# MCU025B_F280049C_Device.net
KiCad netlist of a schematic drawn in Altium Designer
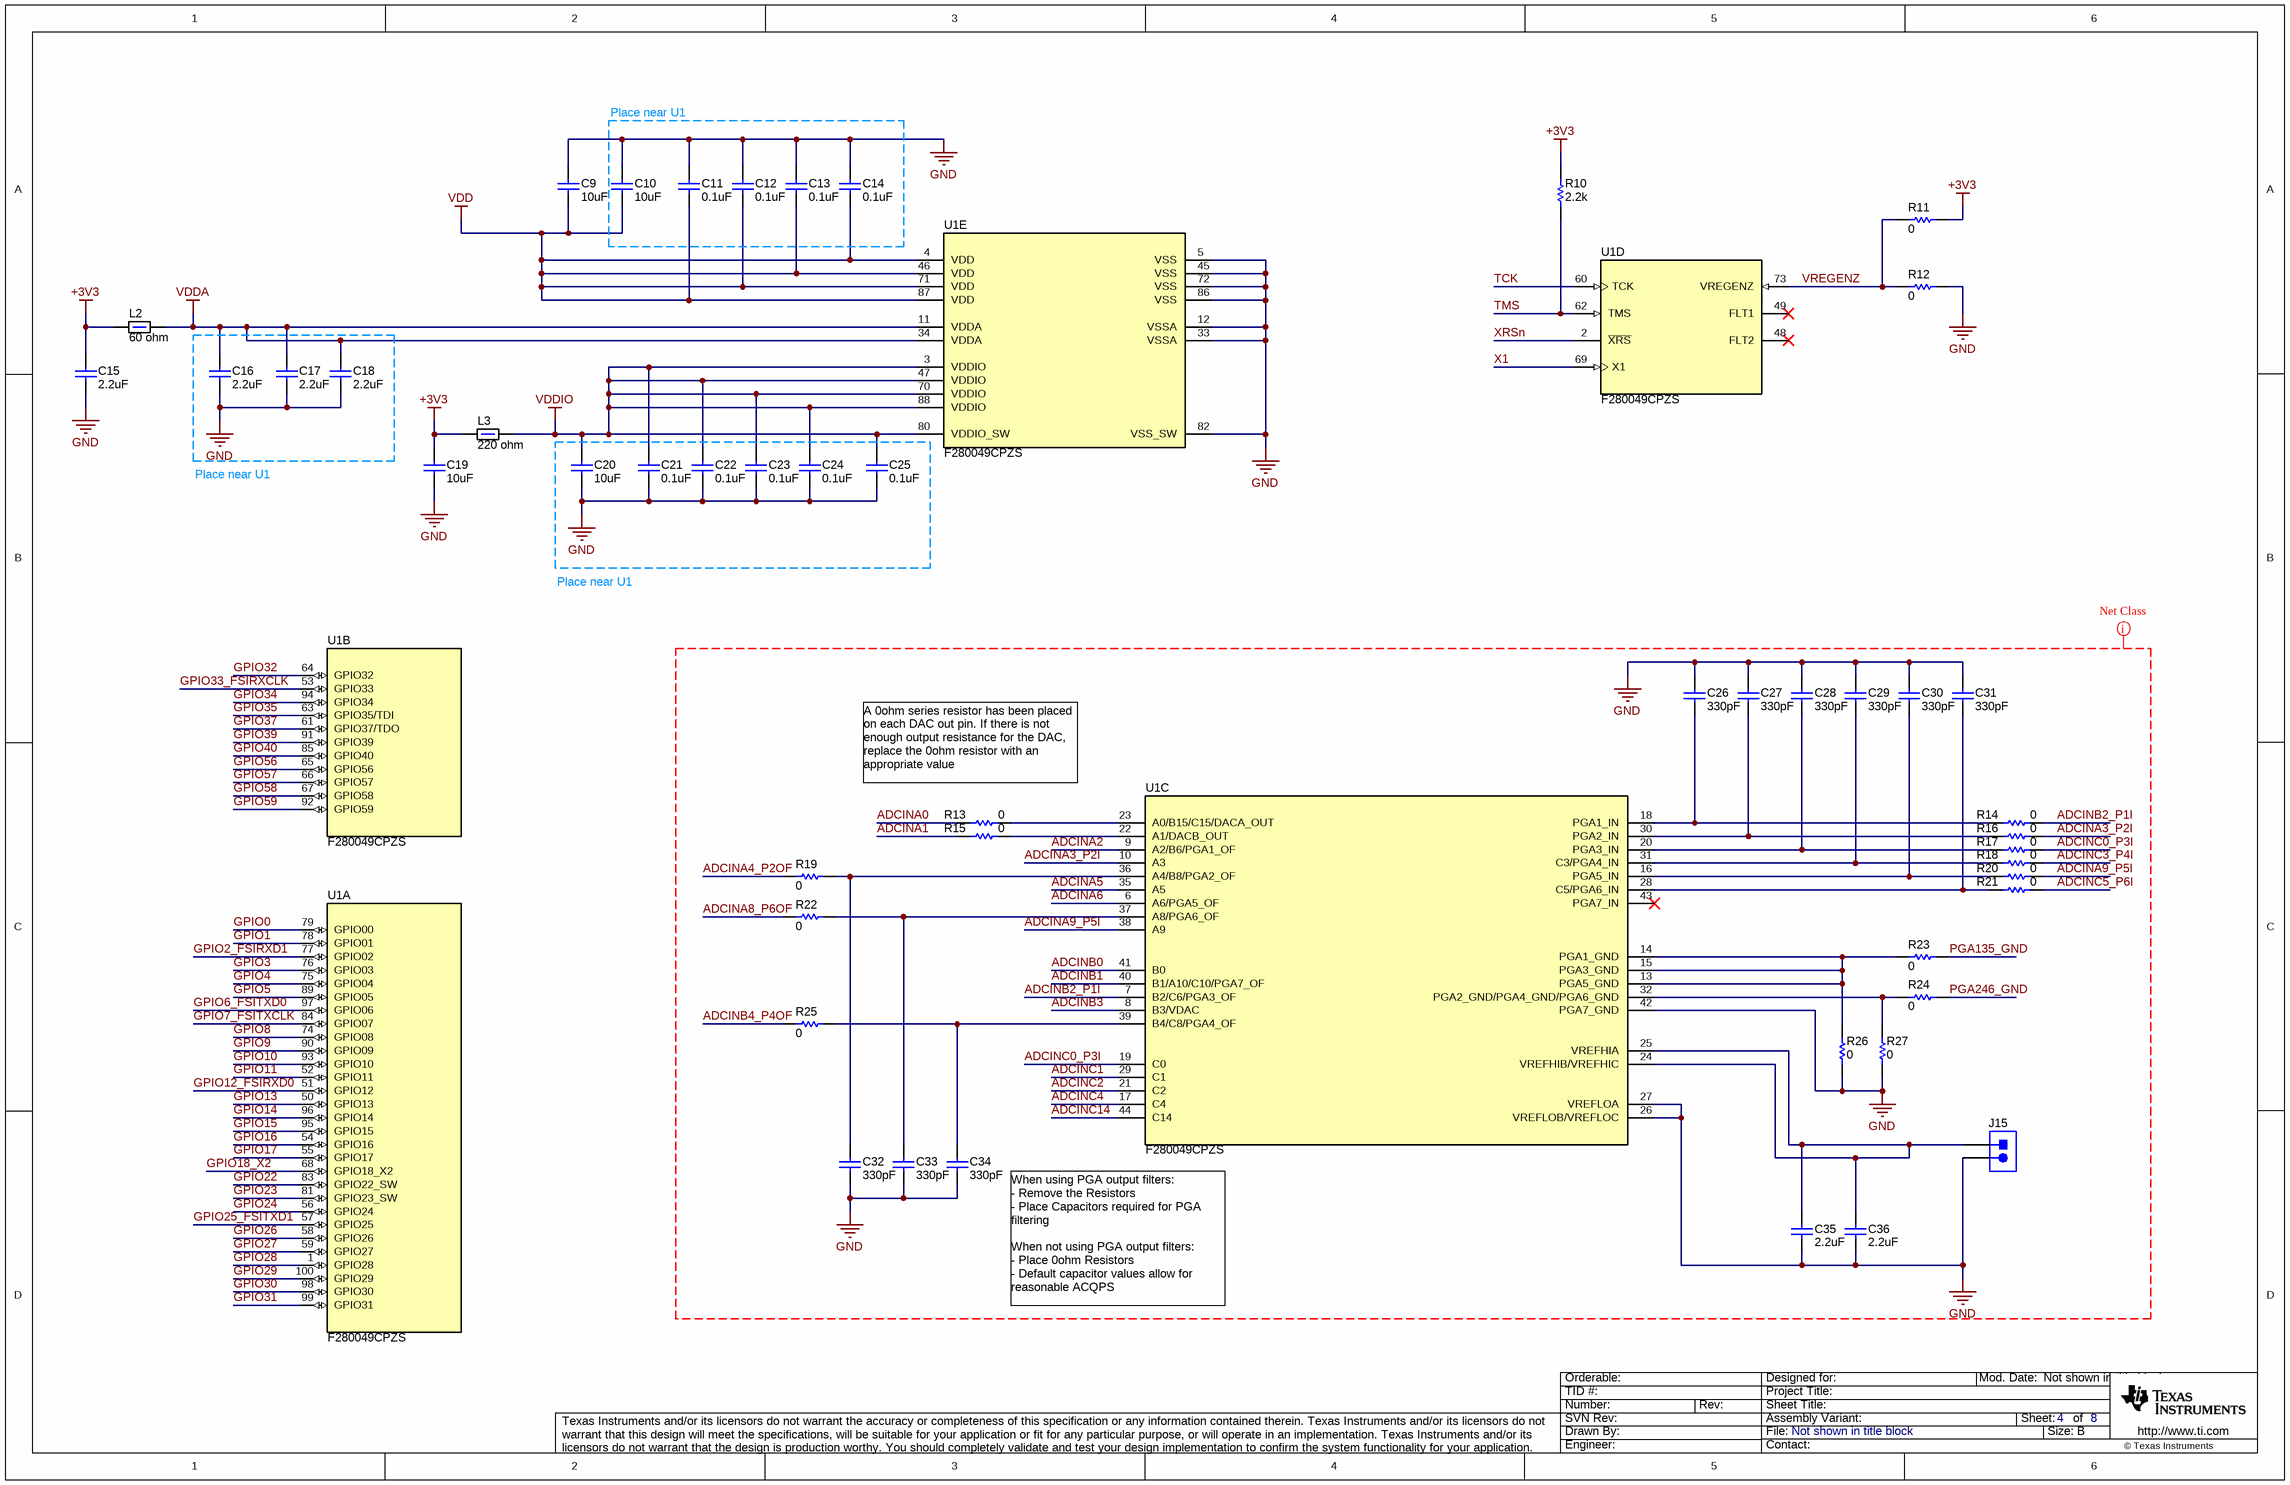
[diagram p0: MCU025B_F280049C_Device.SchDoc]

(export (version "E")
  (design (tool "Eeschema 10.0.6"))
  (components
    (comp (ref "C9")
      (value "GRM188R61A106ME69D")
      (footprint "0603")
      (description "CAP, CERM, 10 uF, 10 V, +/- 20%, X5R, 0603")
      (fields
        (field (name "VALUEDISPLAYED") "10uF")
        (field (name "MANUFACTURER") "MuRata")
        (field (name "PUBLISHER") "Texas Instruments")
      )
      (libsource (lib "Altium Vault - TI") (part "Capacitor"))
    )
    (comp (ref "C10")
      (value "GRM188R61A106ME69D")
      (footprint "0603")
      (description "CAP, CERM, 10 uF, 10 V, +/- 20%, X5R, 0603")
      (fields
        (field (name "VALUEDISPLAYED") "10uF")
        (field (name "MANUFACTURER") "MuRata")
        (field (name "PUBLISHER") "Texas Instruments")
      )
      (libsource (lib "Altium Vault - TI") (part "Capacitor"))
    )
    (comp (ref "C11")
      (value "GRM155R71A104KA01D")
      (footprint "0402")
      (description "CAP, CERM, 0.1 uF, 10 V, +/- 10%, X7R, 0402")
      (fields
        (field (name "VALUEDISPLAYED") "0.1uF")
        (field (name "MANUFACTURER") "MuRata")
        (field (name "PUBLISHER") "Texas Instruments")
      )
      (libsource (lib "Altium Vault - TI") (part "Capacitor"))
    )
    (comp (ref "C12")
      (value "GRM155R71A104KA01D")
      (footprint "0402")
      (description "CAP, CERM, 0.1 uF, 10 V, +/- 10%, X7R, 0402")
      (fields
        (field (name "VALUEDISPLAYED") "0.1uF")
        (field (name "MANUFACTURER") "MuRata")
        (field (name "PUBLISHER") "Texas Instruments")
      )
      (libsource (lib "Altium Vault - TI") (part "Capacitor"))
    )
    (comp (ref "C13")
      (value "GRM155R71A104KA01D")
      (footprint "0402")
      (description "CAP, CERM, 0.1 uF, 10 V, +/- 10%, X7R, 0402")
      (fields
        (field (name "VALUEDISPLAYED") "0.1uF")
        (field (name "MANUFACTURER") "MuRata")
        (field (name "PUBLISHER") "Texas Instruments")
      )
      (libsource (lib "Altium Vault - TI") (part "Capacitor"))
    )
    (comp (ref "C14")
      (value "GRM155R71A104KA01D")
      (footprint "0402")
      (description "CAP, CERM, 0.1 uF, 10 V, +/- 10%, X7R, 0402")
      (fields
        (field (name "VALUEDISPLAYED") "0.1uF")
        (field (name "MANUFACTURER") "MuRata")
        (field (name "PUBLISHER") "Texas Instruments")
      )
      (libsource (lib "Altium Vault - TI") (part "Capacitor"))
    )
    (comp (ref "C15")
      (value "GRM188R61A225KE34D")
      (footprint "0603")
      (description "CAP, CERM, 2.2 uF, 10 V, +/- 10%, X5R, 0603")
      (fields
        (field (name "VALUEDISPLAYED") "2.2uF")
        (field (name "MANUFACTURER") "MuRata")
        (field (name "PUBLISHER") "Texas Instruments")
      )
      (libsource (lib "Altium Vault - TI") (part "Capacitor"))
    )
    (comp (ref "C16")
      (value "GRM188R61A225KE34D")
      (footprint "0603")
      (description "CAP, CERM, 2.2 uF, 10 V, +/- 10%, X5R, 0603")
      (fields
        (field (name "VALUEDISPLAYED") "2.2uF")
        (field (name "MANUFACTURER") "MuRata")
        (field (name "PUBLISHER") "Texas Instruments")
      )
      (libsource (lib "Altium Vault - TI") (part "Capacitor"))
    )
    (comp (ref "C17")
      (value "GRM188R61A225KE34D")
      (footprint "0603")
      (description "CAP, CERM, 2.2 uF, 10 V, +/- 10%, X5R, 0603")
      (fields
        (field (name "VALUEDISPLAYED") "2.2uF")
        (field (name "MANUFACTURER") "MuRata")
        (field (name "PUBLISHER") "Texas Instruments")
      )
      (libsource (lib "Altium Vault - TI") (part "Capacitor"))
    )
    (comp (ref "C18")
      (value "GRM188R61A225KE34D")
      (footprint "0603")
      (description "CAP, CERM, 2.2 uF, 10 V, +/- 10%, X5R, 0603")
      (fields
        (field (name "VALUEDISPLAYED") "2.2uF")
        (field (name "MANUFACTURER") "MuRata")
        (field (name "PUBLISHER") "Texas Instruments")
      )
      (libsource (lib "Altium Vault - TI") (part "Capacitor"))
    )
    (comp (ref "C19")
      (value "GRM188R61A106ME69D")
      (footprint "0603")
      (description "CAP, CERM, 10 uF, 10 V, +/- 20%, X5R, 0603")
      (fields
        (field (name "VALUEDISPLAYED") "10uF")
        (field (name "MANUFACTURER") "MuRata")
        (field (name "PUBLISHER") "Texas Instruments")
      )
      (libsource (lib "Altium Vault - TI") (part "Capacitor"))
    )
    (comp (ref "C20")
      (value "GRM188R61A106ME69D")
      (footprint "0603")
      (description "CAP, CERM, 10 uF, 10 V, +/- 20%, X5R, 0603")
      (fields
        (field (name "VALUEDISPLAYED") "10uF")
        (field (name "MANUFACTURER") "MuRata")
        (field (name "PUBLISHER") "Texas Instruments")
      )
      (libsource (lib "Altium Vault - TI") (part "Capacitor"))
    )
    (comp (ref "C21")
      (value "GRM155R71A104KA01D")
      (footprint "0402")
      (description "CAP, CERM, 0.1 uF, 10 V, +/- 10%, X7R, 0402")
      (fields
        (field (name "VALUEDISPLAYED") "0.1uF")
        (field (name "MANUFACTURER") "MuRata")
        (field (name "PUBLISHER") "Texas Instruments")
      )
      (libsource (lib "Altium Vault - TI") (part "Capacitor"))
    )
    (comp (ref "C22")
      (value "GRM155R71A104KA01D")
      (footprint "0402")
      (description "CAP, CERM, 0.1 uF, 10 V, +/- 10%, X7R, 0402")
      (fields
        (field (name "VALUEDISPLAYED") "0.1uF")
        (field (name "MANUFACTURER") "MuRata")
        (field (name "PUBLISHER") "Texas Instruments")
      )
      (libsource (lib "Altium Vault - TI") (part "Capacitor"))
    )
    (comp (ref "C23")
      (value "GRM155R71A104KA01D")
      (footprint "0402")
      (description "CAP, CERM, 0.1 uF, 10 V, +/- 10%, X7R, 0402")
      (fields
        (field (name "VALUEDISPLAYED") "0.1uF")
        (field (name "MANUFACTURER") "MuRata")
        (field (name "PUBLISHER") "Texas Instruments")
      )
      (libsource (lib "Altium Vault - TI") (part "Capacitor"))
    )
    (comp (ref "C24")
      (value "GRM155R71A104KA01D")
      (footprint "0402")
      (description "CAP, CERM, 0.1 uF, 10 V, +/- 10%, X7R, 0402")
      (fields
        (field (name "VALUEDISPLAYED") "0.1uF")
        (field (name "MANUFACTURER") "MuRata")
        (field (name "PUBLISHER") "Texas Instruments")
      )
      (libsource (lib "Altium Vault - TI") (part "Capacitor"))
    )
    (comp (ref "C25")
      (value "GRM155R71A104KA01D")
      (footprint "0402")
      (description "CAP, CERM, 0.1 uF, 10 V, +/- 10%, X7R, 0402")
      (fields
        (field (name "VALUEDISPLAYED") "0.1uF")
        (field (name "MANUFACTURER") "MuRata")
        (field (name "PUBLISHER") "Texas Instruments")
      )
      (libsource (lib "Altium Vault - TI") (part "Capacitor"))
    )
    (comp (ref "C26")
      (value "GRM1885C1H331JA01D")
      (footprint "0603")
      (description "CAP, CERM, 330 pF, 50 V, +/- 5%, C0G/NP0, 0603")
      (fields
        (field (name "VALUEDISPLAYED") "330pF")
        (field (name "MANUFACTURER") "MuRata")
        (field (name "PUBLISHER") "Texas Instruments")
      )
      (libsource (lib "Altium Vault - TI") (part "Capacitor"))
    )
    (comp (ref "C27")
      (value "GRM1885C1H331JA01D")
      (footprint "0603")
      (description "CAP, CERM, 330 pF, 50 V, +/- 5%, C0G/NP0, 0603")
      (fields
        (field (name "VALUEDISPLAYED") "330pF")
        (field (name "MANUFACTURER") "MuRata")
        (field (name "PUBLISHER") "Texas Instruments")
      )
      (libsource (lib "Altium Vault - TI") (part "Capacitor"))
    )
    (comp (ref "C28")
      (value "GRM1885C1H331JA01D")
      (footprint "0603")
      (description "CAP, CERM, 330 pF, 50 V, +/- 5%, C0G/NP0, 0603")
      (fields
        (field (name "VALUEDISPLAYED") "330pF")
        (field (name "MANUFACTURER") "MuRata")
        (field (name "PUBLISHER") "Texas Instruments")
      )
      (libsource (lib "Altium Vault - TI") (part "Capacitor"))
    )
    (comp (ref "C29")
      (value "GRM1885C1H331JA01D")
      (footprint "0603")
      (description "CAP, CERM, 330 pF, 50 V, +/- 5%, C0G/NP0, 0603")
      (fields
        (field (name "VALUEDISPLAYED") "330pF")
        (field (name "MANUFACTURER") "MuRata")
        (field (name "PUBLISHER") "Texas Instruments")
      )
      (libsource (lib "Altium Vault - TI") (part "Capacitor"))
    )
    (comp (ref "C30")
      (value "GRM1885C1H331JA01D")
      (footprint "0603")
      (description "CAP, CERM, 330 pF, 50 V, +/- 5%, C0G/NP0, 0603")
      (fields
        (field (name "VALUEDISPLAYED") "330pF")
        (field (name "MANUFACTURER") "MuRata")
        (field (name "PUBLISHER") "Texas Instruments")
      )
      (libsource (lib "Altium Vault - TI") (part "Capacitor"))
    )
    (comp (ref "C31")
      (value "GRM1885C1H331JA01D")
      (footprint "0603")
      (description "CAP, CERM, 330 pF, 50 V, +/- 5%, C0G/NP0, 0603")
      (fields
        (field (name "VALUEDISPLAYED") "330pF")
        (field (name "MANUFACTURER") "MuRata")
        (field (name "PUBLISHER") "Texas Instruments")
      )
      (libsource (lib "Altium Vault - TI") (part "Capacitor"))
    )
    (comp (ref "C32")
      (value "GRM1885C1H331JA01D")
      (footprint "0603")
      (description "CAP, CERM, 330 pF, 50 V, +/- 5%, C0G/NP0, 0603")
      (fields
        (field (name "VALUEDISPLAYED") "330pF")
        (field (name "MANUFACTURER") "MuRata")
        (field (name "PUBLISHER") "Texas Instruments")
      )
      (libsource (lib "Altium Vault - TI") (part "Capacitor"))
    )
    (comp (ref "C33")
      (value "GRM1885C1H331JA01D")
      (footprint "0603")
      (description "CAP, CERM, 330 pF, 50 V, +/- 5%, C0G/NP0, 0603")
      (fields
        (field (name "VALUEDISPLAYED") "330pF")
        (field (name "MANUFACTURER") "MuRata")
        (field (name "PUBLISHER") "Texas Instruments")
      )
      (libsource (lib "Altium Vault - TI") (part "Capacitor"))
    )
    (comp (ref "C34")
      (value "GRM1885C1H331JA01D")
      (footprint "0603")
      (description "CAP, CERM, 330 pF, 50 V, +/- 5%, C0G/NP0, 0603")
      (fields
        (field (name "VALUEDISPLAYED") "330pF")
        (field (name "MANUFACTURER") "MuRata")
        (field (name "PUBLISHER") "Texas Instruments")
      )
      (libsource (lib "Altium Vault - TI") (part "Capacitor"))
    )
    (comp (ref "C35")
      (value "GRM188R61A225KE34D")
      (footprint "0603")
      (description "CAP, CERM, 2.2 uF, 10 V, +/- 10%, X5R, 0603")
      (fields
        (field (name "VALUEDISPLAYED") "2.2uF")
        (field (name "MANUFACTURER") "MuRata")
        (field (name "PUBLISHER") "Texas Instruments")
      )
      (libsource (lib "Altium Vault - TI") (part "Capacitor"))
    )
    (comp (ref "C36")
      (value "GRM188R61A225KE34D")
      (footprint "0603")
      (description "CAP, CERM, 2.2 uF, 10 V, +/- 10%, X5R, 0603")
      (fields
        (field (name "VALUEDISPLAYED") "2.2uF")
        (field (name "MANUFACTURER") "MuRata")
        (field (name "PUBLISHER") "Texas Instruments")
      )
      (libsource (lib "Altium Vault - TI") (part "Capacitor"))
    )
    (comp (ref "J15")
      (value "61300211121")
      (footprint "WURTH_61300211121")
      (description "Header, 2.54 mm, 2x1, Gold, TH")
      (fields (field (name "MANUFACTURER") "Wurth Elektronik") (field (name "PUBLISHER") "Texas Instruments"))
      (libsource (lib "Altium Vault - TI") (part "CMP-0054794-1"))
    )
    (comp (ref "L2")
      (value "BKP2125HS600-T")
      (footprint "0805")
      (description "Ferrite Bead, 60 ohm @ 100 MHz, 3 A, 0805")
      (fields
        (field (name "VALUEDISPLAYED") "60 ohm")
        (field (name "MANUFACTURER") "Taiyo Yuden")
        (field (name "PUBLISHER") "Texas Instruments")
      )
      (libsource (lib "Altium Vault - TI") (part "Ferrite_Bead"))
    )
    (comp (ref "L3")
      (value "BLM21PG221SN1D")
      (footprint "0805")
      (description "Ferrite Bead, 220 ohm @ 100 MHz, 2 A, 0805")
      (fields
        (field (name "VALUEDISPLAYED") "220 ohm")
        (field (name "MANUFACTURER") "MuRata")
        (field (name "PUBLISHER") "Texas Instruments")
      )
      (libsource (lib "Altium Vault - TI") (part "Ferrite_Bead"))
    )
    (comp (ref "R10")
      (value "CRCW04022K20JNED")
      (footprint "0402")
      (description "RES, 2.2 k, 5%, 0.063 W, AEC-Q200 Grade 0, 0402")
      (fields (field (name "VALUEDISPLAYED") "2.2k") (field (name "MANUFACTURER") "Vishay-Dale"))
      (libsource (lib "Altium Vault - TI") (part "Resistor"))
    )
    (comp (ref "R11")
      (value "CRCW06030000Z0EA")
      (footprint "0603")
      (description "RES, 0, 5%, 0.1 W, AEC-Q200 Grade 0, 0603")
      (fields (field (name "VALUEDISPLAYED") "0") (field (name "MANUFACTURER") "Vishay-Dale"))
      (libsource (lib "Altium Vault - TI") (part "Resistor"))
    )
    (comp (ref "R12")
      (value "CRCW06030000Z0EA")
      (footprint "0603")
      (description "RES, 0, 5%, 0.1 W, AEC-Q200 Grade 0, 0603")
      (fields (field (name "VALUEDISPLAYED") "0") (field (name "MANUFACTURER") "Vishay-Dale"))
      (libsource (lib "Altium Vault - TI") (part "Resistor"))
    )
    (comp (ref "R13")
      (value "CRCW06030000Z0EA")
      (footprint "0603")
      (description "RES, 0, 5%, 0.1 W, AEC-Q200 Grade 0, 0603")
      (fields (field (name "VALUEDISPLAYED") "0") (field (name "MANUFACTURER") "Vishay-Dale"))
      (libsource (lib "Altium Vault - TI") (part "Resistor"))
    )
    (comp (ref "R14")
      (value "CRCW06030000Z0EA")
      (footprint "0603")
      (description "RES, 0, 5%, 0.1 W, AEC-Q200 Grade 0, 0603")
      (fields (field (name "VALUEDISPLAYED") "0") (field (name "MANUFACTURER") "Vishay-Dale"))
      (libsource (lib "Altium Vault - TI") (part "Resistor"))
    )
    (comp (ref "R15")
      (value "CRCW06030000Z0EA")
      (footprint "0603")
      (description "RES, 0, 5%, 0.1 W, AEC-Q200 Grade 0, 0603")
      (fields (field (name "VALUEDISPLAYED") "0") (field (name "MANUFACTURER") "Vishay-Dale"))
      (libsource (lib "Altium Vault - TI") (part "Resistor"))
    )
    (comp (ref "R16")
      (value "CRCW06030000Z0EA")
      (footprint "0603")
      (description "RES, 0, 5%, 0.1 W, AEC-Q200 Grade 0, 0603")
      (fields (field (name "VALUEDISPLAYED") "0") (field (name "MANUFACTURER") "Vishay-Dale"))
      (libsource (lib "Altium Vault - TI") (part "Resistor"))
    )
    (comp (ref "R17")
      (value "CRCW06030000Z0EA")
      (footprint "0603")
      (description "RES, 0, 5%, 0.1 W, AEC-Q200 Grade 0, 0603")
      (fields (field (name "VALUEDISPLAYED") "0") (field (name "MANUFACTURER") "Vishay-Dale"))
      (libsource (lib "Altium Vault - TI") (part "Resistor"))
    )
    (comp (ref "R18")
      (value "CRCW06030000Z0EA")
      (footprint "0603")
      (description "RES, 0, 5%, 0.1 W, AEC-Q200 Grade 0, 0603")
      (fields (field (name "VALUEDISPLAYED") "0") (field (name "MANUFACTURER") "Vishay-Dale"))
      (libsource (lib "Altium Vault - TI") (part "Resistor"))
    )
    (comp (ref "R19")
      (value "CRCW06030000Z0EA")
      (footprint "0603")
      (description "RES, 0, 5%, 0.1 W, AEC-Q200 Grade 0, 0603")
      (fields (field (name "VALUEDISPLAYED") "0") (field (name "MANUFACTURER") "Vishay-Dale"))
      (libsource (lib "Altium Vault - TI") (part "Resistor"))
    )
    (comp (ref "R20")
      (value "CRCW06030000Z0EA")
      (footprint "0603")
      (description "RES, 0, 5%, 0.1 W, AEC-Q200 Grade 0, 0603")
      (fields (field (name "VALUEDISPLAYED") "0") (field (name "MANUFACTURER") "Vishay-Dale"))
      (libsource (lib "Altium Vault - TI") (part "Resistor"))
    )
    (comp (ref "R21")
      (value "CRCW06030000Z0EA")
      (footprint "0603")
      (description "RES, 0, 5%, 0.1 W, AEC-Q200 Grade 0, 0603")
      (fields (field (name "VALUEDISPLAYED") "0") (field (name "MANUFACTURER") "Vishay-Dale"))
      (libsource (lib "Altium Vault - TI") (part "Resistor"))
    )
    (comp (ref "R22")
      (value "CRCW06030000Z0EA")
      (footprint "0603")
      (description "RES, 0, 5%, 0.1 W, AEC-Q200 Grade 0, 0603")
      (fields (field (name "VALUEDISPLAYED") "0") (field (name "MANUFACTURER") "Vishay-Dale"))
      (libsource (lib "Altium Vault - TI") (part "Resistor"))
    )
    (comp (ref "R23")
      (value "CRCW06030000Z0EA")
      (footprint "0603")
      (description "RES, 0, 5%, 0.1 W, AEC-Q200 Grade 0, 0603")
      (fields (field (name "VALUEDISPLAYED") "0") (field (name "MANUFACTURER") "Vishay-Dale"))
      (libsource (lib "Altium Vault - TI") (part "Resistor"))
    )
    (comp (ref "R24")
      (value "CRCW06030000Z0EA")
      (footprint "0603")
      (description "RES, 0, 5%, 0.1 W, AEC-Q200 Grade 0, 0603")
      (fields (field (name "VALUEDISPLAYED") "0") (field (name "MANUFACTURER") "Vishay-Dale"))
      (libsource (lib "Altium Vault - TI") (part "Resistor"))
    )
    (comp (ref "R25")
      (value "CRCW06030000Z0EA")
      (footprint "0603")
      (description "RES, 0, 5%, 0.1 W, AEC-Q200 Grade 0, 0603")
      (fields (field (name "VALUEDISPLAYED") "0") (field (name "MANUFACTURER") "Vishay-Dale"))
      (libsource (lib "Altium Vault - TI") (part "Resistor"))
    )
    (comp (ref "R26")
      (value "CRCW06030000Z0EA")
      (footprint "0603")
      (description "RES, 0, 5%, 0.1 W, AEC-Q200 Grade 0, 0603")
      (fields (field (name "VALUEDISPLAYED") "0") (field (name "MANUFACTURER") "Vishay-Dale"))
      (libsource (lib "Altium Vault - TI") (part "Resistor"))
    )
    (comp (ref "R27")
      (value "CRCW06030000Z0EA")
      (footprint "0603")
      (description "RES, 0, 5%, 0.1 W, AEC-Q200 Grade 0, 0603")
      (fields (field (name "VALUEDISPLAYED") "0") (field (name "MANUFACTURER") "Vishay-Dale"))
      (libsource (lib "Altium Vault - TI") (part "Resistor"))
    )
    (comp (ref "U1")
      (value "F280049CPZS")
      (footprint "PZ0100A_N")
      (description "Piccolo Microcontroller, PZ0100A (LQFP-100)")
      (fields (field (name "PARTNUMBER") "F280049CPZS") (field (name "MANUFACTURER") "Texas Instruments"))
      (libsource (lib "Altium Vault - TI") (part "F280049PZ"))
    )
  )
  (nets
    (net (code "1") (name "+3V3") (class "Default")
      (node (ref "C15") (pin "1") (pinfunction "1_1") (pintype "passive"))
      (node (ref "C19") (pin "1") (pinfunction "1_1") (pintype "passive"))
      (node (ref "L2") (pin "1") (pinfunction "1_1") (pintype "passive"))
      (node (ref "L3") (pin "1") (pinfunction "1_1") (pintype "passive"))
      (node (ref "R10") (pin "2") (pinfunction "2_2") (pintype "passive"))
      (node (ref "R11") (pin "2") (pinfunction "2_2") (pintype "passive"))
    )
    (net (code "2") (name "/ADCINA0") (class "Default")
      (node (ref "R13") (pin "1") (pinfunction "1_1") (pintype "passive"))
    )
    (net (code "3") (name "/ADCINA1") (class "Default")
      (node (ref "R15") (pin "1") (pinfunction "1_1") (pintype "passive"))
    )
    (net (code "4") (name "/ADCINA2") (class "Default")
      (node (ref "U1") (pin "9") (pinfunction "A2/B6/PGA1_OF_9") (pintype "passive"))
    )
    (net (code "5") (name "/ADCINA3_P2I") (class "Default")
      (node (ref "R16") (pin "2") (pinfunction "2_2") (pintype "passive"))
      (node (ref "U1") (pin "10") (pinfunction "A3_10") (pintype "passive"))
    )
    (net (code "6") (name "/ADCINA4_P2OF") (class "Default")
      (node (ref "R19") (pin "1") (pinfunction "1_1") (pintype "passive"))
    )
    (net (code "7") (name "/ADCINA5") (class "Default")
      (node (ref "U1") (pin "35") (pinfunction "A5_35") (pintype "passive"))
    )
    (net (code "8") (name "/ADCINA6") (class "Default")
      (node (ref "U1") (pin "6") (pinfunction "A6/PGA5_OF_6") (pintype "passive"))
    )
    (net (code "9") (name "/ADCINA8_P6OF") (class "Default")
      (node (ref "R22") (pin "1") (pinfunction "1_1") (pintype "passive"))
    )
    (net (code "10") (name "/ADCINA9_P5I") (class "Default")
      (node (ref "R20") (pin "2") (pinfunction "2_2") (pintype "passive"))
      (node (ref "U1") (pin "38") (pinfunction "A9_38") (pintype "passive"))
    )
    (net (code "11") (name "/ADCINB0") (class "Default")
      (node (ref "U1") (pin "41") (pinfunction "B0_41") (pintype "passive"))
    )
    (net (code "12") (name "/ADCINB1") (class "Default")
      (node (ref "U1") (pin "40") (pinfunction "B1/A10/C10/PGA7_OF_40") (pintype "passive"))
    )
    (net (code "13") (name "/ADCINB2_P1I") (class "Default")
      (node (ref "R14") (pin "2") (pinfunction "2_2") (pintype "passive"))
      (node (ref "U1") (pin "7") (pinfunction "B2/C6/PGA3_OF_7") (pintype "passive"))
    )
    (net (code "14") (name "/ADCINB3") (class "Default")
      (node (ref "U1") (pin "8") (pinfunction "B3/VDAC_8") (pintype "passive"))
    )
    (net (code "15") (name "/ADCINB4_P4OF") (class "Default")
      (node (ref "R25") (pin "1") (pinfunction "1_1") (pintype "passive"))
    )
    (net (code "16") (name "/ADCINC0_P3I") (class "Default")
      (node (ref "R17") (pin "2") (pinfunction "2_2") (pintype "passive"))
      (node (ref "U1") (pin "19") (pinfunction "C0_19") (pintype "passive"))
    )
    (net (code "17") (name "/ADCINC1") (class "Default")
      (node (ref "U1") (pin "29") (pinfunction "C1_29") (pintype "passive"))
    )
    (net (code "18") (name "/ADCINC2") (class "Default")
      (node (ref "U1") (pin "21") (pinfunction "C2_21") (pintype "passive"))
    )
    (net (code "19") (name "/ADCINC3_P4I") (class "Default")
      (node (ref "R18") (pin "2") (pinfunction "2_2") (pintype "passive"))
    )
    (net (code "20") (name "/ADCINC4") (class "Default")
      (node (ref "U1") (pin "17") (pinfunction "C4_17") (pintype "passive"))
    )
    (net (code "21") (name "/ADCINC5_P6I") (class "Default")
      (node (ref "R21") (pin "2") (pinfunction "2_2") (pintype "passive"))
    )
    (net (code "22") (name "/ADCINC14") (class "Default")
      (node (ref "U1") (pin "44") (pinfunction "C14_44") (pintype "passive"))
    )
    (net (code "23") (name "/GPIO0") (class "Default")
      (node (ref "U1") (pin "79") (pinfunction "GPIO00_79") (pintype "bidirectional"))
    )
    (net (code "24") (name "/GPIO1") (class "Default")
      (node (ref "U1") (pin "78") (pinfunction "GPIO01_78") (pintype "bidirectional"))
    )
    (net (code "25") (name "/GPIO2_FSIRXD1") (class "Default")
      (node (ref "U1") (pin "77") (pinfunction "GPIO02_77") (pintype "bidirectional"))
    )
    (net (code "26") (name "/GPIO3") (class "Default")
      (node (ref "U1") (pin "76") (pinfunction "GPIO03_76") (pintype "bidirectional"))
    )
    (net (code "27") (name "/GPIO4") (class "Default")
      (node (ref "U1") (pin "75") (pinfunction "GPIO04_75") (pintype "bidirectional"))
    )
    (net (code "28") (name "/GPIO5") (class "Default")
      (node (ref "U1") (pin "89") (pinfunction "GPIO05_89") (pintype "bidirectional"))
    )
    (net (code "29") (name "/GPIO6_FSITXD0") (class "Default")
      (node (ref "U1") (pin "97") (pinfunction "GPIO06_97") (pintype "bidirectional"))
    )
    (net (code "30") (name "/GPIO7_FSITXCLK") (class "Default")
      (node (ref "U1") (pin "84") (pinfunction "GPIO07_84") (pintype "bidirectional"))
    )
    (net (code "31") (name "/GPIO8") (class "Default")
      (node (ref "U1") (pin "74") (pinfunction "GPIO08_74") (pintype "bidirectional"))
    )
    (net (code "32") (name "/GPIO9") (class "Default")
      (node (ref "U1") (pin "90") (pinfunction "GPIO09_90") (pintype "bidirectional"))
    )
    (net (code "33") (name "/GPIO10") (class "Default")
      (node (ref "U1") (pin "93") (pinfunction "GPIO10_93") (pintype "bidirectional"))
    )
    (net (code "34") (name "/GPIO11") (class "Default")
      (node (ref "U1") (pin "52") (pinfunction "GPIO11_52") (pintype "bidirectional"))
    )
    (net (code "35") (name "/GPIO12_FSIRXD0") (class "Default")
      (node (ref "U1") (pin "51") (pinfunction "GPIO12_51") (pintype "bidirectional"))
    )
    (net (code "36") (name "/GPIO13") (class "Default")
      (node (ref "U1") (pin "50") (pinfunction "GPIO13_50") (pintype "bidirectional"))
    )
    (net (code "37") (name "/GPIO14") (class "Default")
      (node (ref "U1") (pin "96") (pinfunction "GPIO14_96") (pintype "bidirectional"))
    )
    (net (code "38") (name "/GPIO15") (class "Default")
      (node (ref "U1") (pin "95") (pinfunction "GPIO15_95") (pintype "bidirectional"))
    )
    (net (code "39") (name "/GPIO16") (class "Default")
      (node (ref "U1") (pin "54") (pinfunction "GPIO16_54") (pintype "bidirectional"))
    )
    (net (code "40") (name "/GPIO17") (class "Default")
      (node (ref "U1") (pin "55") (pinfunction "GPIO17_55") (pintype "bidirectional"))
    )
    (net (code "41") (name "/GPIO18_X2") (class "Default")
      (node (ref "U1") (pin "68") (pinfunction "GPIO18_X2_68") (pintype "bidirectional"))
    )
    (net (code "42") (name "/GPIO22") (class "Default")
      (node (ref "U1") (pin "83") (pinfunction "GPIO22_SW_83") (pintype "bidirectional"))
    )
    (net (code "43") (name "/GPIO23") (class "Default")
      (node (ref "U1") (pin "81") (pinfunction "GPIO23_SW_81") (pintype "bidirectional"))
    )
    (net (code "44") (name "/GPIO24") (class "Default")
      (node (ref "U1") (pin "56") (pinfunction "GPIO24_56") (pintype "bidirectional"))
    )
    (net (code "45") (name "/GPIO25_FSITXD1") (class "Default")
      (node (ref "U1") (pin "57") (pinfunction "GPIO25_57") (pintype "bidirectional"))
    )
    (net (code "46") (name "/GPIO26") (class "Default")
      (node (ref "U1") (pin "58") (pinfunction "GPIO26_58") (pintype "bidirectional"))
    )
    (net (code "47") (name "/GPIO27") (class "Default")
      (node (ref "U1") (pin "59") (pinfunction "GPIO27_59") (pintype "bidirectional"))
    )
    (net (code "48") (name "/GPIO28") (class "Default")
      (node (ref "U1") (pin "1") (pinfunction "GPIO28_1") (pintype "bidirectional"))
    )
    (net (code "49") (name "/GPIO29") (class "Default")
      (node (ref "U1") (pin "100") (pinfunction "GPIO29_100") (pintype "bidirectional"))
    )
    (net (code "50") (name "/GPIO30") (class "Default")
      (node (ref "U1") (pin "98") (pinfunction "GPIO30_98") (pintype "bidirectional"))
    )
    (net (code "51") (name "/GPIO31") (class "Default")
      (node (ref "U1") (pin "99") (pinfunction "GPIO31_99") (pintype "bidirectional"))
    )
    (net (code "52") (name "/GPIO32") (class "Default")
      (node (ref "U1") (pin "64") (pinfunction "GPIO32_64") (pintype "bidirectional"))
    )
    (net (code "53") (name "/GPIO33_FSIRXCLK") (class "Default")
      (node (ref "U1") (pin "53") (pinfunction "GPIO33_53") (pintype "bidirectional"))
    )
    (net (code "54") (name "/GPIO34") (class "Default")
      (node (ref "U1") (pin "94") (pinfunction "GPIO34_94") (pintype "bidirectional"))
    )
    (net (code "55") (name "/GPIO35") (class "Default")
      (node (ref "U1") (pin "63") (pinfunction "GPIO35/TDI_63") (pintype "bidirectional"))
    )
    (net (code "56") (name "/GPIO37") (class "Default")
      (node (ref "U1") (pin "61") (pinfunction "GPIO37/TDO_61") (pintype "bidirectional"))
    )
    (net (code "57") (name "/GPIO39") (class "Default")
      (node (ref "U1") (pin "91") (pinfunction "GPIO39_91") (pintype "bidirectional"))
    )
    (net (code "58") (name "/GPIO40") (class "Default")
      (node (ref "U1") (pin "85") (pinfunction "GPIO40_85") (pintype "bidirectional"))
    )
    (net (code "59") (name "/GPIO56") (class "Default")
      (node (ref "U1") (pin "65") (pinfunction "GPIO56_65") (pintype "bidirectional"))
    )
    (net (code "60") (name "/GPIO57") (class "Default")
      (node (ref "U1") (pin "66") (pinfunction "GPIO57_66") (pintype "bidirectional"))
    )
    (net (code "61") (name "/GPIO58") (class "Default")
      (node (ref "U1") (pin "67") (pinfunction "GPIO58_67") (pintype "bidirectional"))
    )
    (net (code "62") (name "/GPIO59") (class "Default")
      (node (ref "U1") (pin "92") (pinfunction "GPIO59_92") (pintype "bidirectional"))
    )
    (net (code "63") (name "/PGA135_GND") (class "Default")
      (node (ref "R23") (pin "2") (pinfunction "2_2") (pintype "passive"))
    )
    (net (code "64") (name "/PGA246_GND") (class "Default")
      (node (ref "R24") (pin "2") (pinfunction "2_2") (pintype "passive"))
    )
    (net (code "65") (name "/TCK") (class "Default")
      (node (ref "U1") (pin "60") (pinfunction "TCK_60") (pintype "input"))
    )
    (net (code "66") (name "/TMS") (class "Default")
      (node (ref "R10") (pin "1") (pinfunction "1_1") (pintype "passive"))
      (node (ref "U1") (pin "62") (pinfunction "TMS_62") (pintype "input"))
    )
    (net (code "67") (name "/VREGENZ") (class "Default")
      (node (ref "R11") (pin "1") (pinfunction "1_1") (pintype "passive"))
      (node (ref "R12") (pin "1") (pinfunction "1_1") (pintype "passive"))
      (node (ref "U1") (pin "73") (pinfunction "VREGENZ_73") (pintype "input"))
    )
    (net (code "68") (name "/X1") (class "Default")
      (node (ref "U1") (pin "69") (pinfunction "X1_69") (pintype "input"))
    )
    (net (code "69") (name "/XRSn") (class "Default")
      (node (ref "U1") (pin "2") (pinfunction "XRS_2") (pintype "open_collector"))
    )
    (net (code "70") (name "GND") (class "Default")
      (node (ref "C10") (pin "1") (pinfunction "1_1") (pintype "passive"))
      (node (ref "C11") (pin "2") (pinfunction "2_2") (pintype "passive"))
      (node (ref "C12") (pin "2") (pinfunction "2_2") (pintype "passive"))
      (node (ref "C13") (pin "2") (pinfunction "2_2") (pintype "passive"))
      (node (ref "C14") (pin "2") (pinfunction "2_2") (pintype "passive"))
      (node (ref "C15") (pin "2") (pinfunction "2_2") (pintype "passive"))
      (node (ref "C16") (pin "2") (pinfunction "2_2") (pintype "passive"))
      (node (ref "C17") (pin "2") (pinfunction "2_2") (pintype "passive"))
      (node (ref "C18") (pin "2") (pinfunction "2_2") (pintype "passive"))
      (node (ref "C19") (pin "2") (pinfunction "2_2") (pintype "passive"))
      (node (ref "C20") (pin "2") (pinfunction "2_2") (pintype "passive"))
      (node (ref "C21") (pin "1") (pinfunction "1_1") (pintype "passive"))
      (node (ref "C22") (pin "1") (pinfunction "1_1") (pintype "passive"))
      (node (ref "C23") (pin "1") (pinfunction "1_1") (pintype "passive"))
      (node (ref "C24") (pin "1") (pinfunction "1_1") (pintype "passive"))
      (node (ref "C25") (pin "1") (pinfunction "1_1") (pintype "passive"))
      (node (ref "C26") (pin "1") (pinfunction "1_1") (pintype "passive"))
      (node (ref "C27") (pin "1") (pinfunction "1_1") (pintype "passive"))
      (node (ref "C28") (pin "1") (pinfunction "1_1") (pintype "passive"))
      (node (ref "C29") (pin "1") (pinfunction "1_1") (pintype "passive"))
      (node (ref "C30") (pin "1") (pinfunction "1_1") (pintype "passive"))
      (node (ref "C31") (pin "1") (pinfunction "1_1") (pintype "passive"))
      (node (ref "C32") (pin "2") (pinfunction "2_2") (pintype "passive"))
      (node (ref "C33") (pin "2") (pinfunction "2_2") (pintype "passive"))
      (node (ref "C34") (pin "2") (pinfunction "2_2") (pintype "passive"))
      (node (ref "C35") (pin "2") (pinfunction "2_2") (pintype "passive"))
      (node (ref "C36") (pin "2") (pinfunction "2_2") (pintype "passive"))
      (node (ref "C9") (pin "1") (pinfunction "1_1") (pintype "passive"))
      (node (ref "J15") (pin "2") (pinfunction "2_2") (pintype "passive"))
      (node (ref "R12") (pin "2") (pinfunction "2_2") (pintype "passive"))
      (node (ref "R26") (pin "1") (pinfunction "1_1") (pintype "passive"))
      (node (ref "R27") (pin "1") (pinfunction "1_1") (pintype "passive"))
      (node (ref "U1") (pin "12") (pinfunction "VSSA_12") (pintype "power_in"))
      (node (ref "U1") (pin "26") (pinfunction "VREFLOB/VREFLOC_26") (pintype "passive"))
      (node (ref "U1") (pin "27") (pinfunction "VREFLOA_27") (pintype "passive"))
      (node (ref "U1") (pin "33") (pinfunction "VSSA_33") (pintype "power_in"))
      (node (ref "U1") (pin "42") (pinfunction "PGA7_GND_42") (pintype "passive"))
      (node (ref "U1") (pin "45") (pinfunction "VSS_45") (pintype "power_in"))
      (node (ref "U1") (pin "5") (pinfunction "VSS_5") (pintype "power_in"))
      (node (ref "U1") (pin "72") (pinfunction "VSS_72") (pintype "power_in"))
      (node (ref "U1") (pin "82") (pinfunction "VSS_SW_82") (pintype "power_in"))
      (node (ref "U1") (pin "86") (pinfunction "VSS_86") (pintype "power_in"))
    )
    (net (code "71") (name "Net-(U1C-A0{slash}B15{slash}C15{slash}DACA_OUT)") (class "Default")
      (node (ref "R13") (pin "2") (pinfunction "2_2") (pintype "passive"))
      (node (ref "U1") (pin "23") (pinfunction "A0/B15/C15/DACA_OUT_23") (pintype "passive"))
    )
    (net (code "72") (name "Net-(U1C-A1{slash}DACB_OUT)") (class "Default")
      (node (ref "R15") (pin "2") (pinfunction "2_2") (pintype "passive"))
      (node (ref "U1") (pin "22") (pinfunction "A1/DACB_OUT_22") (pintype "passive"))
    )
    (net (code "73") (name "Net-(U1C-A4{slash}B8{slash}PGA2_OF)") (class "Default")
      (node (ref "C32") (pin "1") (pinfunction "1_1") (pintype "passive"))
      (node (ref "R19") (pin "2") (pinfunction "2_2") (pintype "passive"))
      (node (ref "U1") (pin "36") (pinfunction "A4/B8/PGA2_OF_36") (pintype "passive"))
    )
    (net (code "74") (name "Net-(U1C-A8{slash}PGA6_OF)") (class "Default")
      (node (ref "C33") (pin "1") (pinfunction "1_1") (pintype "passive"))
      (node (ref "R22") (pin "2") (pinfunction "2_2") (pintype "passive"))
      (node (ref "U1") (pin "37") (pinfunction "A8/PGA6_OF_37") (pintype "passive"))
    )
    (net (code "75") (name "Net-(U1C-B4{slash}C8{slash}PGA4_OF)") (class "Default")
      (node (ref "C34") (pin "1") (pinfunction "1_1") (pintype "passive"))
      (node (ref "R25") (pin "2") (pinfunction "2_2") (pintype "passive"))
      (node (ref "U1") (pin "39") (pinfunction "B4/C8/PGA4_OF_39") (pintype "passive"))
    )
    (net (code "76") (name "Net-(U1C-C3{slash}PGA4_IN)") (class "Default")
      (node (ref "C29") (pin "2") (pinfunction "2_2") (pintype "passive"))
      (node (ref "R18") (pin "1") (pinfunction "1_1") (pintype "passive"))
      (node (ref "U1") (pin "31") (pinfunction "C3/PGA4_IN_31") (pintype "passive"))
    )
    (net (code "77") (name "Net-(U1C-C5{slash}PGA6_IN)") (class "Default")
      (node (ref "C31") (pin "2") (pinfunction "2_2") (pintype "passive"))
      (node (ref "R21") (pin "1") (pinfunction "1_1") (pintype "passive"))
      (node (ref "U1") (pin "28") (pinfunction "C5/PGA6_IN_28") (pintype "passive"))
    )
    (net (code "78") (name "Net-(U1C-PGA1_GND)") (class "Default")
      (node (ref "R23") (pin "1") (pinfunction "1_1") (pintype "passive"))
      (node (ref "R26") (pin "2") (pinfunction "2_2") (pintype "passive"))
      (node (ref "U1") (pin "13") (pinfunction "PGA5_GND_13") (pintype "passive"))
      (node (ref "U1") (pin "14") (pinfunction "PGA1_GND_14") (pintype "passive"))
      (node (ref "U1") (pin "15") (pinfunction "PGA3_GND_15") (pintype "passive"))
    )
    (net (code "79") (name "Net-(U1C-PGA1_IN)") (class "Default")
      (node (ref "C26") (pin "2") (pinfunction "2_2") (pintype "passive"))
      (node (ref "R14") (pin "1") (pinfunction "1_1") (pintype "passive"))
      (node (ref "U1") (pin "18") (pinfunction "PGA1_IN_18") (pintype "passive"))
    )
    (net (code "80") (name "Net-(U1C-PGA2_GND{slash}PGA4_GND{slash}PGA6_GND)") (class "Default")
      (node (ref "R24") (pin "1") (pinfunction "1_1") (pintype "passive"))
      (node (ref "R27") (pin "2") (pinfunction "2_2") (pintype "passive"))
      (node (ref "U1") (pin "32") (pinfunction "PGA2_GND/PGA4_GND/PGA6_GND_32") (pintype "passive"))
    )
    (net (code "81") (name "Net-(U1C-PGA2_IN)") (class "Default")
      (node (ref "C27") (pin "2") (pinfunction "2_2") (pintype "passive"))
      (node (ref "R16") (pin "1") (pinfunction "1_1") (pintype "passive"))
      (node (ref "U1") (pin "30") (pinfunction "PGA2_IN_30") (pintype "passive"))
    )
    (net (code "82") (name "Net-(U1C-PGA3_IN)") (class "Default")
      (node (ref "C28") (pin "2") (pinfunction "2_2") (pintype "passive"))
      (node (ref "R17") (pin "1") (pinfunction "1_1") (pintype "passive"))
      (node (ref "U1") (pin "20") (pinfunction "PGA3_IN_20") (pintype "passive"))
    )
    (net (code "83") (name "Net-(U1C-PGA5_IN)") (class "Default")
      (node (ref "C30") (pin "2") (pinfunction "2_2") (pintype "passive"))
      (node (ref "R20") (pin "1") (pinfunction "1_1") (pintype "passive"))
      (node (ref "U1") (pin "16") (pinfunction "PGA5_IN_16") (pintype "passive"))
    )
    (net (code "84") (name "Net-(U1C-VREFHIA)") (class "Default")
      (node (ref "C35") (pin "1") (pinfunction "1_1") (pintype "passive"))
      (node (ref "C36") (pin "1") (pinfunction "1_1") (pintype "passive"))
      (node (ref "J15") (pin "1") (pinfunction "1_1") (pintype "passive"))
      (node (ref "U1") (pin "24") (pinfunction "VREFHIB/VREFHIC_24") (pintype "passive"))
      (node (ref "U1") (pin "25") (pinfunction "VREFHIA_25") (pintype "passive"))
    )
    (net (code "85") (name "VDD") (class "Default")
      (node (ref "C10") (pin "2") (pinfunction "2_2") (pintype "passive"))
      (node (ref "C11") (pin "1") (pinfunction "1_1") (pintype "passive"))
      (node (ref "C12") (pin "1") (pinfunction "1_1") (pintype "passive"))
      (node (ref "C13") (pin "1") (pinfunction "1_1") (pintype "passive"))
      (node (ref "C14") (pin "1") (pinfunction "1_1") (pintype "passive"))
      (node (ref "C9") (pin "2") (pinfunction "2_2") (pintype "passive"))
      (node (ref "U1") (pin "4") (pinfunction "VDD_4") (pintype "power_in"))
      (node (ref "U1") (pin "46") (pinfunction "VDD_46") (pintype "power_in"))
      (node (ref "U1") (pin "71") (pinfunction "VDD_71") (pintype "power_in"))
      (node (ref "U1") (pin "87") (pinfunction "VDD_87") (pintype "power_in"))
    )
    (net (code "86") (name "VDDA") (class "Default")
      (node (ref "C16") (pin "1") (pinfunction "1_1") (pintype "passive"))
      (node (ref "C17") (pin "1") (pinfunction "1_1") (pintype "passive"))
      (node (ref "C18") (pin "1") (pinfunction "1_1") (pintype "passive"))
      (node (ref "L2") (pin "2") (pinfunction "2_2") (pintype "passive"))
      (node (ref "U1") (pin "11") (pinfunction "VDDA_11") (pintype "power_in"))
      (node (ref "U1") (pin "34") (pinfunction "VDDA_34") (pintype "power_in"))
    )
    (net (code "87") (name "VDDIO") (class "Default")
      (node (ref "C20") (pin "1") (pinfunction "1_1") (pintype "passive"))
      (node (ref "C21") (pin "2") (pinfunction "2_2") (pintype "passive"))
      (node (ref "C22") (pin "2") (pinfunction "2_2") (pintype "passive"))
      (node (ref "C23") (pin "2") (pinfunction "2_2") (pintype "passive"))
      (node (ref "C24") (pin "2") (pinfunction "2_2") (pintype "passive"))
      (node (ref "C25") (pin "2") (pinfunction "2_2") (pintype "passive"))
      (node (ref "L3") (pin "2") (pinfunction "2_2") (pintype "passive"))
      (node (ref "U1") (pin "3") (pinfunction "VDDIO_3") (pintype "power_in"))
      (node (ref "U1") (pin "47") (pinfunction "VDDIO_47") (pintype "power_in"))
      (node (ref "U1") (pin "70") (pinfunction "VDDIO_70") (pintype "power_in"))
      (node (ref "U1") (pin "80") (pinfunction "VDDIO_SW_80") (pintype "power_in"))
      (node (ref "U1") (pin "88") (pinfunction "VDDIO_88") (pintype "power_in"))
    )
    (net (code "88") (name "unconnected-(U1C-PGA7_IN-Pad43)") (class "Default")
      (node (ref "U1") (pin "43") (pinfunction "PGA7_IN_43") (pintype "passive+no_connect"))
    )
    (net (code "89") (name "unconnected-(U1D-FLT1-Pad49)") (class "Default")
      (node (ref "U1") (pin "49") (pinfunction "FLT1_49") (pintype "passive+no_connect"))
    )
    (net (code "90") (name "unconnected-(U1D-FLT2-Pad48)") (class "Default")
      (node (ref "U1") (pin "48") (pinfunction "FLT2_48") (pintype "passive+no_connect"))
    )
  )
)
